# Pg2-Current_Sense.net
KiCad netlist of a schematic drawn in Altium Designer
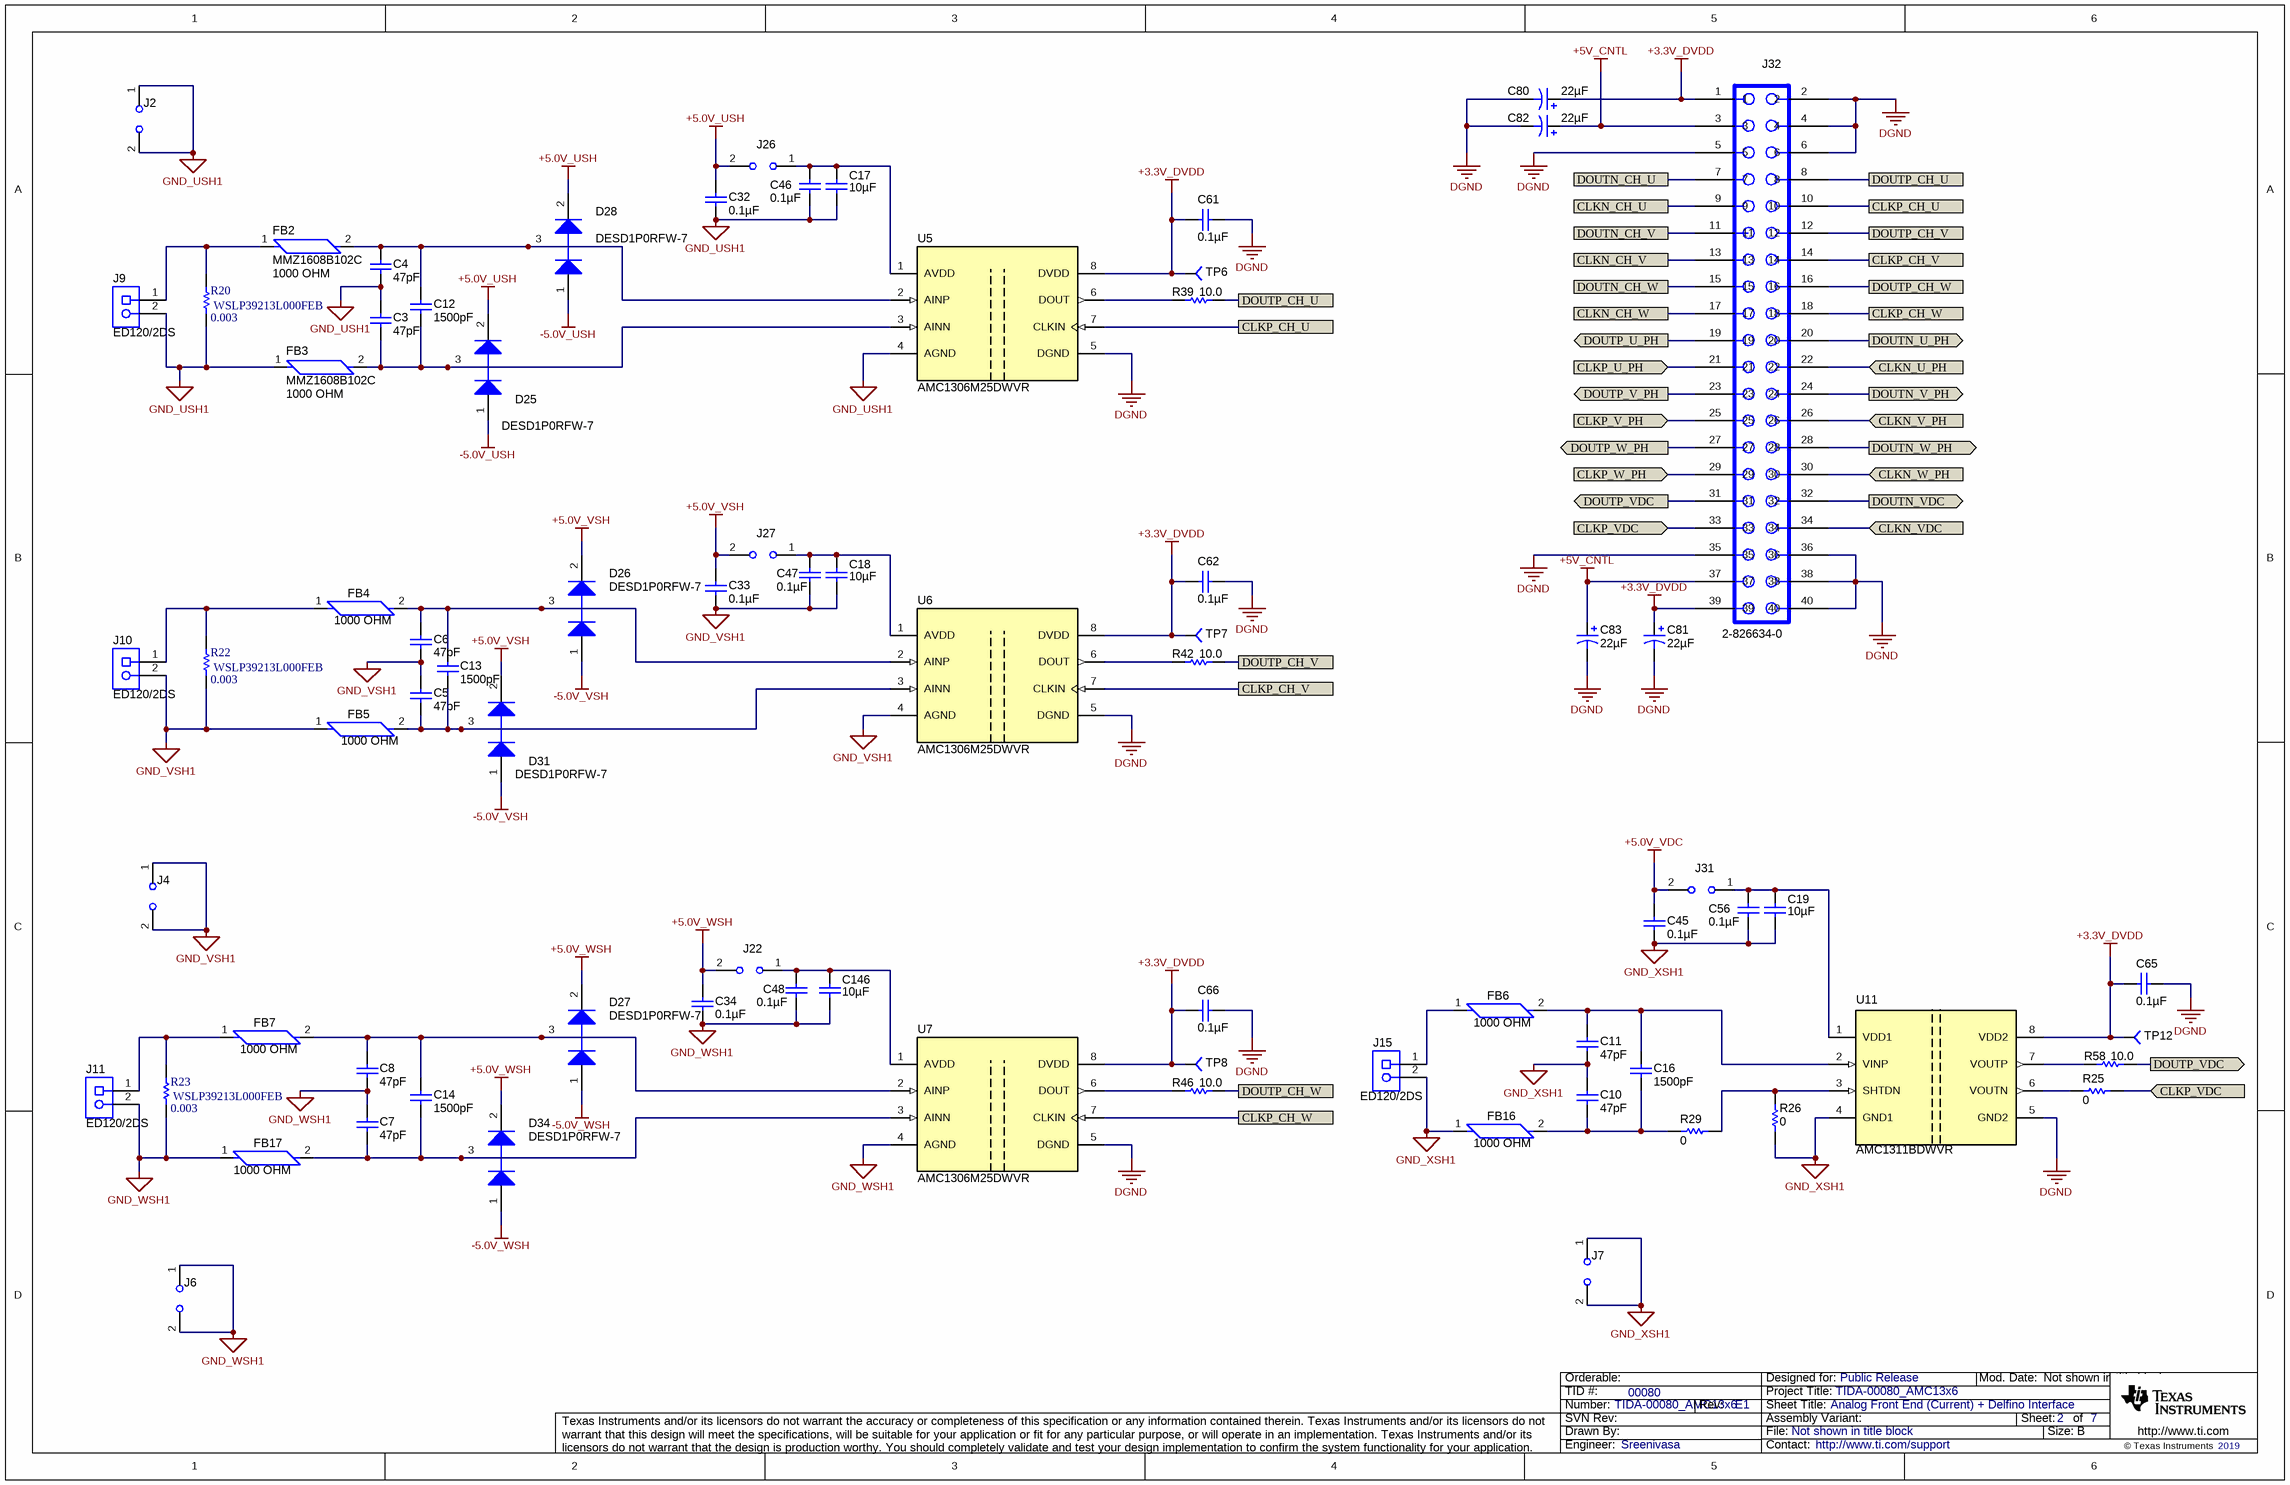
[diagram p0: Pg2-Current Sense.SchDoc]

(export (version "E")
  (design (tool "Eeschema 10.0.6"))
  (components
    (comp (ref "C3")
      (value "GRM21A5C2E470JW01D")
      (footprint "ISE_MCS_SDM_E1_20MAY:0805_HV")
      (description "CAP, CERM, 47pF, 500V, +/-5%, C0G/NP0, 0805")
      (fields
        (field (name "VALUEDISPLAYED") "47pF")
        (field (name "MANUFACTURER") "MuRata")
        (field (name "PUBLISHER") "Texas Instruments")
      )
      (libsource (lib "Capacitor_Ceramic") (part "GRM21A5C2E470JW01D"))
    )
    (comp (ref "C4")
      (value "GRM21A5C2E470JW01D")
      (footprint "ISE_MCS_SDM_E1_20MAY:0805_HV")
      (description "CAP, CERM, 47pF, 500V, +/-5%, C0G/NP0, 0805")
      (fields
        (field (name "VALUEDISPLAYED") "47pF")
        (field (name "MANUFACTURER") "MuRata")
        (field (name "PUBLISHER") "Texas Instruments")
      )
      (libsource (lib "Capacitor_Ceramic") (part "GRM21A5C2E470JW01D"))
    )
    (comp (ref "C5")
      (value "GRM21A5C2E470JW01D")
      (footprint "ISE_MCS_SDM_E1_20MAY:0805_HV")
      (description "CAP, CERM, 47pF, 500V, +/-5%, C0G/NP0, 0805")
      (fields
        (field (name "VALUEDISPLAYED") "47pF")
        (field (name "MANUFACTURER") "MuRata")
        (field (name "PUBLISHER") "Texas Instruments")
      )
      (libsource (lib "Capacitor_Ceramic") (part "GRM21A5C2E470JW01D"))
    )
    (comp (ref "C6")
      (value "GRM21A5C2E470JW01D")
      (footprint "ISE_MCS_SDM_E1_20MAY:0805_HV")
      (description "CAP, CERM, 47pF, 500V, +/-5%, C0G/NP0, 0805")
      (fields
        (field (name "VALUEDISPLAYED") "47pF")
        (field (name "MANUFACTURER") "MuRata")
        (field (name "PUBLISHER") "Texas Instruments")
      )
      (libsource (lib "Capacitor_Ceramic") (part "GRM21A5C2E470JW01D"))
    )
    (comp (ref "C7")
      (value "GRM21A5C2E470JW01D")
      (footprint "ISE_MCS_SDM_E1_20MAY:0805_HV")
      (description "CAP, CERM, 47pF, 500V, +/-5%, C0G/NP0, 0805")
      (fields
        (field (name "VALUEDISPLAYED") "47pF")
        (field (name "MANUFACTURER") "MuRata")
        (field (name "PUBLISHER") "Texas Instruments")
      )
      (libsource (lib "Capacitor_Ceramic") (part "GRM21A5C2E470JW01D"))
    )
    (comp (ref "C8")
      (value "GRM21A5C2E470JW01D")
      (footprint "ISE_MCS_SDM_E1_20MAY:0805_HV")
      (description "CAP, CERM, 47pF, 500V, +/-5%, C0G/NP0, 0805")
      (fields
        (field (name "VALUEDISPLAYED") "47pF")
        (field (name "MANUFACTURER") "MuRata")
        (field (name "PUBLISHER") "Texas Instruments")
      )
      (libsource (lib "Capacitor_Ceramic") (part "GRM21A5C2E470JW01D"))
    )
    (comp (ref "C10")
      (value "GRM21A5C2E470JW01D")
      (footprint "ISE_MCS_SDM_E1_20MAY:0805_HV")
      (description "CAP, CERM, 47pF, 500V, +/-5%, C0G/NP0, 0805")
      (fields
        (field (name "VALUEDISPLAYED") "47pF")
        (field (name "MANUFACTURER") "MuRata")
        (field (name "PUBLISHER") "Texas Instruments")
      )
      (libsource (lib "Capacitor_Ceramic") (part "GRM21A5C2E470JW01D"))
    )
    (comp (ref "C11")
      (value "GRM21A5C2E470JW01D")
      (footprint "ISE_MCS_SDM_E1_20MAY:0805_HV")
      (description "CAP, CERM, 47pF, 500V, +/-5%, C0G/NP0, 0805")
      (fields
        (field (name "VALUEDISPLAYED") "47pF")
        (field (name "MANUFACTURER") "MuRata")
        (field (name "PUBLISHER") "Texas Instruments")
      )
      (libsource (lib "Capacitor_Ceramic") (part "GRM21A5C2E470JW01D"))
    )
    (comp (ref "C12")
      (value "06031C152KAT2A")
      (footprint "ISE_MCS_SDM_E1_20MAY:0603")
      (description "CAP, CERM, 1500pF, 100V, +/-10%, X7R, 0603")
      (fields
        (field (name "VALUEDISPLAYED") "1500pF")
        (field (name "MANUFACTURER") "AVX")
        (field (name "PUBLISHER") "Texas Instruments")
      )
      (libsource (lib "Capacitor_Ceramic") (part "06031C152KAT2A"))
    )
    (comp (ref "C13")
      (value "06031C152KAT2A")
      (footprint "ISE_MCS_SDM_E1_20MAY:0603")
      (description "CAP, CERM, 1500pF, 100V, +/-10%, X7R, 0603")
      (fields
        (field (name "VALUEDISPLAYED") "1500pF")
        (field (name "MANUFACTURER") "AVX")
        (field (name "PUBLISHER") "Texas Instruments")
      )
      (libsource (lib "Capacitor_Ceramic") (part "06031C152KAT2A"))
    )
    (comp (ref "C14")
      (value "06031C152KAT2A")
      (footprint "ISE_MCS_SDM_E1_20MAY:0603")
      (description "CAP, CERM, 1500pF, 100V, +/-10%, X7R, 0603")
      (fields
        (field (name "VALUEDISPLAYED") "1500pF")
        (field (name "MANUFACTURER") "AVX")
        (field (name "PUBLISHER") "Texas Instruments")
      )
      (libsource (lib "Capacitor_Ceramic") (part "06031C152KAT2A"))
    )
    (comp (ref "C16")
      (value "06031C152KAT2A")
      (footprint "ISE_MCS_SDM_E1_20MAY:0603")
      (description "CAP, CERM, 1500pF, 100V, +/-10%, X7R, 0603")
      (fields
        (field (name "VALUEDISPLAYED") "1500pF")
        (field (name "MANUFACTURER") "AVX")
        (field (name "PUBLISHER") "Texas Instruments")
      )
      (libsource (lib "Capacitor_Ceramic") (part "06031C152KAT2A"))
    )
    (comp (ref "C17")
      (value "~")
      (footprint "1210")
      (description "CAP, CERM, 10uF, 35V, +/-20%, X7R, 1210")
      (fields
        (field (name "PARTNUMBER") "GMK325AB7106MM-T")
        (field (name "VALUEDISPLAYED") "10µF")
        (field (name "MANUFACTURER") "Taiyo Yuden")
        (field (name "PUBLISHER") "Texas Instruments")
      )
      (libsource (lib "Capacitor_Ceramic") (part "GMK325AB7106MM-T"))
    )
    (comp (ref "C18")
      (value "~")
      (footprint "1210")
      (description "CAP, CERM, 10uF, 35V, +/-20%, X7R, 1210")
      (fields
        (field (name "PARTNUMBER") "GMK325AB7106MM-T")
        (field (name "VALUEDISPLAYED") "10µF")
        (field (name "MANUFACTURER") "Taiyo Yuden")
        (field (name "PUBLISHER") "Texas Instruments")
      )
      (libsource (lib "Capacitor_Ceramic") (part "GMK325AB7106MM-T"))
    )
    (comp (ref "C19")
      (value "~")
      (footprint "1210")
      (description "CAP, CERM, 10uF, 35V, +/-20%, X7R, 1210")
      (fields
        (field (name "PARTNUMBER") "GMK325AB7106MM-T")
        (field (name "VALUEDISPLAYED") "10µF")
        (field (name "MANUFACTURER") "Taiyo Yuden")
        (field (name "PUBLISHER") "Texas Instruments")
      )
      (libsource (lib "Capacitor_Ceramic") (part "GMK325AB7106MM-T"))
    )
    (comp (ref "C32")
      (value "~")
      (footprint "ISE_MCS_SDM_E1_20MAY:0603")
      (description "CAP, CERM, 0.1uF, 50V, +/-10%, X7R, 0603")
      (fields
        (field (name "PARTNUMBER") "C0603C104K5RACTU")
        (field (name "VALUEDISPLAYED") "0.1µF")
        (field (name "MANUFACTURER") "Kemet")
        (field (name "PUBLISHER") "Texas Instruments")
      )
      (libsource (lib "Capacitor_Ceramic") (part "C0603C104K5RACTU"))
    )
    (comp (ref "C33")
      (value "~")
      (footprint "ISE_MCS_SDM_E1_20MAY:0603")
      (description "CAP, CERM, 0.1uF, 50V, +/-10%, X7R, 0603")
      (fields
        (field (name "PARTNUMBER") "C0603C104K5RACTU")
        (field (name "VALUEDISPLAYED") "0.1µF")
        (field (name "MANUFACTURER") "Kemet")
        (field (name "PUBLISHER") "Texas Instruments")
      )
      (libsource (lib "Capacitor_Ceramic") (part "C0603C104K5RACTU"))
    )
    (comp (ref "C34")
      (value "~")
      (footprint "ISE_MCS_SDM_E1_20MAY:0603")
      (description "CAP, CERM, 0.1uF, 50V, +/-10%, X7R, 0603")
      (fields
        (field (name "PARTNUMBER") "C0603C104K5RACTU")
        (field (name "VALUEDISPLAYED") "0.1µF")
        (field (name "MANUFACTURER") "Kemet")
        (field (name "PUBLISHER") "Texas Instruments")
      )
      (libsource (lib "Capacitor_Ceramic") (part "C0603C104K5RACTU"))
    )
    (comp (ref "C45")
      (value "~")
      (footprint "ISE_MCS_SDM_E1_20MAY:0603")
      (description "CAP, CERM, 0.1uF, 50V, +/-10%, X7R, 0603")
      (fields
        (field (name "PARTNUMBER") "C0603C104K5RACTU")
        (field (name "VALUEDISPLAYED") "0.1µF")
        (field (name "MANUFACTURER") "Kemet")
        (field (name "PUBLISHER") "Texas Instruments")
      )
      (libsource (lib "Capacitor_Ceramic") (part "C0603C104K5RACTU"))
    )
    (comp (ref "C46")
      (value "~")
      (footprint "ISE_MCS_SDM_E1_20MAY:0603")
      (description "CAP, CERM, 0.1uF, 50V, +/-10%, X7R, 0603")
      (fields
        (field (name "PARTNUMBER") "C0603C104K5RACTU")
        (field (name "VALUEDISPLAYED") "0.1µF")
        (field (name "MANUFACTURER") "Kemet")
        (field (name "PUBLISHER") "Texas Instruments")
      )
      (libsource (lib "Capacitor_Ceramic") (part "C0603C104K5RACTU"))
    )
    (comp (ref "C47")
      (value "~")
      (footprint "ISE_MCS_SDM_E1_20MAY:0603")
      (description "CAP, CERM, 0.1uF, 50V, +/-10%, X7R, 0603")
      (fields
        (field (name "PARTNUMBER") "C0603C104K5RACTU")
        (field (name "VALUEDISPLAYED") "0.1µF")
        (field (name "MANUFACTURER") "Kemet")
        (field (name "PUBLISHER") "Texas Instruments")
      )
      (libsource (lib "Capacitor_Ceramic") (part "C0603C104K5RACTU"))
    )
    (comp (ref "C48")
      (value "~")
      (footprint "ISE_MCS_SDM_E1_20MAY:0603")
      (description "CAP, CERM, 0.1uF, 50V, +/-10%, X7R, 0603")
      (fields
        (field (name "PARTNUMBER") "C0603C104K5RACTU")
        (field (name "VALUEDISPLAYED") "0.1µF")
        (field (name "MANUFACTURER") "Kemet")
        (field (name "PUBLISHER") "Texas Instruments")
      )
      (libsource (lib "Capacitor_Ceramic") (part "C0603C104K5RACTU"))
    )
    (comp (ref "C56")
      (value "~")
      (footprint "ISE_MCS_SDM_E1_20MAY:0603")
      (description "CAP, CERM, 0.1uF, 50V, +/-10%, X7R, 0603")
      (fields
        (field (name "PARTNUMBER") "C0603C104K5RACTU")
        (field (name "VALUEDISPLAYED") "0.1µF")
        (field (name "MANUFACTURER") "Kemet")
        (field (name "PUBLISHER") "Texas Instruments")
      )
      (libsource (lib "Capacitor_Ceramic") (part "C0603C104K5RACTU"))
    )
    (comp (ref "C61")
      (value "~")
      (footprint "ISE_MCS_SDM_E1_20MAY:0603")
      (description "CAP, CERM, 0.1uF, 25V, +/-5%, X7R, 0603")
      (fields
        (field (name "PARTNUMBER") "06033C104JAT2A")
        (field (name "VALUEDISPLAYED") "0.1µF")
        (field (name "MANUFACTURER") "AVX")
        (field (name "PUBLISHER") "Texas Instruments")
      )
      (libsource (lib "Capacitor_Ceramic") (part "06033C104JAT2A"))
    )
    (comp (ref "C62")
      (value "~")
      (footprint "ISE_MCS_SDM_E1_20MAY:0603")
      (description "CAP, CERM, 0.1uF, 25V, +/-5%, X7R, 0603")
      (fields
        (field (name "PARTNUMBER") "06033C104JAT2A")
        (field (name "VALUEDISPLAYED") "0.1µF")
        (field (name "MANUFACTURER") "AVX")
        (field (name "PUBLISHER") "Texas Instruments")
      )
      (libsource (lib "Capacitor_Ceramic") (part "06033C104JAT2A"))
    )
    (comp (ref "C65")
      (value "~")
      (footprint "ISE_MCS_SDM_E1_20MAY:0603")
      (description "CAP, CERM, 0.1uF, 25V, +/-5%, X7R, 0603")
      (fields
        (field (name "PARTNUMBER") "06033C104JAT2A")
        (field (name "VALUEDISPLAYED") "0.1µF")
        (field (name "MANUFACTURER") "AVX")
        (field (name "PUBLISHER") "Texas Instruments")
      )
      (libsource (lib "Capacitor_Ceramic") (part "06033C104JAT2A"))
    )
    (comp (ref "C66")
      (value "~")
      (footprint "ISE_MCS_SDM_E1_20MAY:0603")
      (description "CAP, CERM, 0.1uF, 25V, +/-5%, X7R, 0603")
      (fields
        (field (name "PARTNUMBER") "06033C104JAT2A")
        (field (name "VALUEDISPLAYED") "0.1µF")
        (field (name "MANUFACTURER") "AVX")
        (field (name "PUBLISHER") "Texas Instruments")
      )
      (libsource (lib "Capacitor_Ceramic") (part "06033C104JAT2A"))
    )
    (comp (ref "C80")
      (value "UUD1E220MCL1GS")
      (footprint "ISE_MCS_SDM_E1_20MAY:SM_RADIAL_5MM")
      (description "CAP, AL, 22uF, 25V, +/-20%, 0.76 ohm, SMD")
      (fields
        (field (name "VALUEDISPLAYED") "22µF")
        (field (name "MANUFACTURER") "Nichicon")
        (field (name "PUBLISHER") "Texas Instruments")
      )
      (libsource (lib "Capacitor_Aluminum") (part "UUD1E220MCL1GS"))
    )
    (comp (ref "C81")
      (value "UUD1E220MCL1GS")
      (footprint "ISE_MCS_SDM_E1_20MAY:SM_RADIAL_5MM")
      (description "CAP, AL, 22uF, 25V, +/-20%, 0.76 ohm, SMD")
      (fields
        (field (name "VALUEDISPLAYED") "22µF")
        (field (name "MANUFACTURER") "Nichicon")
        (field (name "PUBLISHER") "Texas Instruments")
      )
      (libsource (lib "Capacitor_Aluminum") (part "UUD1E220MCL1GS"))
    )
    (comp (ref "C82")
      (value "UUD1E220MCL1GS")
      (footprint "ISE_MCS_SDM_E1_20MAY:SM_RADIAL_5MM")
      (description "CAP, AL, 22uF, 25V, +/-20%, 0.76 ohm, SMD")
      (fields
        (field (name "VALUEDISPLAYED") "22µF")
        (field (name "MANUFACTURER") "Nichicon")
        (field (name "PUBLISHER") "Texas Instruments")
      )
      (libsource (lib "Capacitor_Aluminum") (part "UUD1E220MCL1GS"))
    )
    (comp (ref "C83")
      (value "UUD1E220MCL1GS")
      (footprint "ISE_MCS_SDM_E1_20MAY:SM_RADIAL_5MM")
      (description "CAP, AL, 22uF, 25V, +/-20%, 0.76 ohm, SMD")
      (fields
        (field (name "VALUEDISPLAYED") "22µF")
        (field (name "MANUFACTURER") "Nichicon")
        (field (name "PUBLISHER") "Texas Instruments")
      )
      (libsource (lib "Capacitor_Aluminum") (part "UUD1E220MCL1GS"))
    )
    (comp (ref "C146")
      (value "~")
      (footprint "1210")
      (description "CAP, CERM, 10uF, 35V, +/-20%, X7R, 1210")
      (fields
        (field (name "PARTNUMBER") "GMK325AB7106MM-T")
        (field (name "VALUEDISPLAYED") "10µF")
        (field (name "MANUFACTURER") "Taiyo Yuden")
        (field (name "PUBLISHER") "Texas Instruments")
      )
      (libsource (lib "Capacitor_Ceramic") (part "GMK325AB7106MM-T"))
    )
    (comp (ref "D25")
      (value "DESD1P0RFW-7")
      (footprint "ISE_MCS_SDM_E1_20MAY:SOT-323")
      (description "Diode, P-N, 70V, 0.2A, SOT-323")
      (fields (field (name "MANUFACTURER") "Diodes Inc") (field (name "PUBLISHER") "Texas Instruments"))
      (libsource (lib "Diode") (part "BAV99WT1G"))
    )
    (comp (ref "D26")
      (value "DESD1P0RFW-7")
      (footprint "ISE_MCS_SDM_E1_20MAY:SOT-323")
      (description "Diode, P-N, 70V, 0.2A, SOT-323")
      (fields (field (name "MANUFACTURER") "Diodes Inc") (field (name "PUBLISHER") "Texas Instruments"))
      (libsource (lib "Diode") (part "BAV99WT1G"))
    )
    (comp (ref "D27")
      (value "DESD1P0RFW-7")
      (footprint "ISE_MCS_SDM_E1_20MAY:SOT-323")
      (description "Diode, P-N, 70V, 0.2A, SOT-323")
      (fields (field (name "MANUFACTURER") "Diodes Inc") (field (name "PUBLISHER") "Texas Instruments"))
      (libsource (lib "Diode") (part "BAV99WT1G"))
    )
    (comp (ref "D28")
      (value "DESD1P0RFW-7")
      (footprint "ISE_MCS_SDM_E1_20MAY:SOT-323")
      (description "Diode, P-N, 70V, 0.2A, SOT-323")
      (fields (field (name "MANUFACTURER") "Diodes Inc") (field (name "PUBLISHER") "Texas Instruments"))
      (libsource (lib "Diode") (part "BAV99WT1G"))
    )
    (comp (ref "D31")
      (value "DESD1P0RFW-7")
      (footprint "ISE_MCS_SDM_E1_20MAY:SOT-323")
      (description "Diode, P-N, 70V, 0.2A, SOT-323")
      (fields (field (name "MANUFACTURER") "Diodes Inc") (field (name "PUBLISHER") "Texas Instruments"))
      (libsource (lib "Diode") (part "BAV99WT1G"))
    )
    (comp (ref "D34")
      (value "DESD1P0RFW-7")
      (footprint "ISE_MCS_SDM_E1_20MAY:SOT-323")
      (description "Diode, P-N, 70V, 0.2A, SOT-323")
      (fields (field (name "MANUFACTURER") "Diodes Inc") (field (name "PUBLISHER") "Texas Instruments"))
      (libsource (lib "Diode") (part "BAV99WT1G"))
    )
    (comp (ref "FB2")
      (value "MMZ1608B102C")
      (footprint "FB0603")
      (description "FERRITE CHIP 1000 OHM 300MA 0603")
      (fields
        (field (name "MANUFACTURER") "TDK Corporation")
        (field (name "ALTIUM_VALUE") "1000 OHM")
        (field (name "PUBLISHER") "TI")
      )
      (libsource (lib "Isolated current sensing") (part "MMZ1608B102C"))
    )
    (comp (ref "FB3")
      (value "MMZ1608B102C")
      (footprint "FB0603")
      (description "FERRITE CHIP 1000 OHM 300MA 0603")
      (fields
        (field (name "MANUFACTURER") "TDK Corporation")
        (field (name "ALTIUM_VALUE") "1000 OHM")
        (field (name "PUBLISHER") "TI")
      )
      (libsource (lib "Isolated current sensing") (part "MMZ1608B102C"))
    )
    (comp (ref "FB4")
      (value "1000 OHM")
      (footprint "FB0603")
      (description "FERRITE CHIP 1000 OHM 300MA 0603")
      (fields
        (field (name "PARTNUMBER") "MMZ1608B102C")
        (field (name "MANUFACTURER") "TDK Corporation")
        (field (name "PUBLISHER") "TI")
      )
      (libsource (lib "Isolated current sensing") (part "MMZ1608B102C"))
    )
    (comp (ref "FB5")
      (value "1000 OHM")
      (footprint "FB0603")
      (description "FERRITE CHIP 1000 OHM 300MA 0603")
      (fields
        (field (name "PARTNUMBER") "MMZ1608B102C")
        (field (name "MANUFACTURER") "TDK Corporation")
        (field (name "PUBLISHER") "TI")
      )
      (libsource (lib "Isolated current sensing") (part "MMZ1608B102C"))
    )
    (comp (ref "FB6")
      (value "1000 OHM")
      (footprint "FB0603")
      (description "FERRITE CHIP 1000 OHM 300MA 0603")
      (fields
        (field (name "PARTNUMBER") "MMZ1608B102C")
        (field (name "MANUFACTURER") "TDK Corporation")
        (field (name "PUBLISHER") "TI")
      )
      (libsource (lib "Isolated current sensing") (part "MMZ1608B102C"))
    )
    (comp (ref "FB7")
      (value "1000 OHM")
      (footprint "FB0603")
      (description "FERRITE CHIP 1000 OHM 300MA 0603")
      (fields
        (field (name "PARTNUMBER") "MMZ1608B102C")
        (field (name "MANUFACTURER") "TDK Corporation")
        (field (name "PUBLISHER") "TI")
      )
      (libsource (lib "Isolated current sensing") (part "MMZ1608B102C"))
    )
    (comp (ref "FB16")
      (value "1000 OHM")
      (footprint "FB0603")
      (description "FERRITE CHIP 1000 OHM 300MA 0603")
      (fields
        (field (name "PARTNUMBER") "MMZ1608B102C")
        (field (name "MANUFACTURER") "TDK Corporation")
        (field (name "PUBLISHER") "TI")
      )
      (libsource (lib "Isolated current sensing") (part "MMZ1608B102C"))
    )
    (comp (ref "FB17")
      (value "1000 OHM")
      (footprint "FB0603")
      (description "FERRITE CHIP 1000 OHM 300MA 0603")
      (fields
        (field (name "PARTNUMBER") "MMZ1608B102C")
        (field (name "MANUFACTURER") "TDK Corporation")
        (field (name "PUBLISHER") "TI")
      )
      (libsource (lib "Isolated current sensing") (part "MMZ1608B102C"))
    )
    (comp (ref "J2")
      (value "~")
      (footprint "ISE_MCS_SDM_E1_20MAY:HDR100_1X2")
      (description "Header, Male 2-pin, 100mil spacing,")
      (fields (field (name "MANUFACTURER") "FCI") (field (name "PARTNUMBER") "68001-402HLF"))
      (libsource (lib "PADSlegacy_Hardware") (part "JUMPER_2X100MIL"))
    )
    (comp (ref "J4")
      (value "~")
      (footprint "ISE_MCS_SDM_E1_20MAY:HDR100_1X2")
      (description "Header, Male 2-pin, 100mil spacing,")
      (fields (field (name "MANUFACTURER") "FCI") (field (name "PARTNUMBER") "68001-402HLF"))
      (libsource (lib "PADSlegacy_Hardware") (part "JUMPER_2X100MIL"))
    )
    (comp (ref "J6")
      (value "~")
      (footprint "ISE_MCS_SDM_E1_20MAY:HDR100_1X2")
      (description "Header, Male 2-pin, 100mil spacing,")
      (fields (field (name "MANUFACTURER") "FCI") (field (name "PARTNUMBER") "68001-402HLF"))
      (libsource (lib "PADSlegacy_Hardware") (part "JUMPER_2X100MIL"))
    )
    (comp (ref "J7")
      (value "~")
      (footprint "ISE_MCS_SDM_E1_20MAY:HDR100_1X2")
      (description "Header, Male 2-pin, 100mil spacing,")
      (fields (field (name "MANUFACTURER") "FCI") (field (name "PARTNUMBER") "68001-402HLF"))
      (libsource (lib "PADSlegacy_Hardware") (part "JUMPER_2X100MIL"))
    )
    (comp (ref "J9")
      (value "ED120/2DS")
      (footprint "ISE_MCS_SDM_E1_20MAY:CONN_ED120-2DS")
      (description "TERMINAL BLOCK 5.08MM VERT 2POS, TH")
      (fields
        (field (name "MANUFACTURER") "On-Shore Technology")
        (field (name "SYMBOLCREATOR") "a0412235")
        (field (name "PUBLISHER") "Texas Instruments")
      )
      (libsource (lib "Connectors") (part "ED120/2DS"))
    )
    (comp (ref "J10")
      (value "ED120/2DS")
      (footprint "ISE_MCS_SDM_E1_20MAY:CONN_ED120-2DS")
      (description "TERMINAL BLOCK 5.08MM VERT 2POS, TH")
      (fields
        (field (name "MANUFACTURER") "On-Shore Technology")
        (field (name "SYMBOLCREATOR") "a0412235")
        (field (name "PUBLISHER") "Texas Instruments")
      )
      (libsource (lib "Connectors") (part "ED120/2DS"))
    )
    (comp (ref "J11")
      (value "ED120/2DS")
      (footprint "ISE_MCS_SDM_E1_20MAY:CONN_ED120-2DS")
      (description "TERMINAL BLOCK 5.08MM VERT 2POS, TH")
      (fields
        (field (name "MANUFACTURER") "On-Shore Technology")
        (field (name "SYMBOLCREATOR") "a0412235")
        (field (name "PUBLISHER") "Texas Instruments")
      )
      (libsource (lib "Connectors") (part "ED120/2DS"))
    )
    (comp (ref "J15")
      (value "ED120/2DS")
      (footprint "ISE_MCS_SDM_E1_20MAY:CONN_ED120-2DS")
      (description "TERMINAL BLOCK 5.08MM VERT 2POS, TH")
      (fields
        (field (name "MANUFACTURER") "On-Shore Technology")
        (field (name "SYMBOLCREATOR") "a0412235")
        (field (name "PUBLISHER") "Texas Instruments")
      )
      (libsource (lib "Connectors") (part "ED120/2DS"))
    )
    (comp (ref "J22")
      (value "~")
      (footprint "ISE_MCS_SDM_E1_20MAY:HDR100_1X2")
      (description "Header, Male 2-pin, 100mil spacing,")
      (fields (field (name "MANUFACTURER") "FCI") (field (name "PARTNUMBER") "68001-402HLF"))
      (libsource (lib "PADSlegacy_Hardware") (part "JUMPER_2X100MIL"))
    )
    (comp (ref "J26")
      (value "~")
      (footprint "ISE_MCS_SDM_E1_20MAY:HDR100_1X2")
      (description "Header, Male 2-pin, 100mil spacing,")
      (fields (field (name "MANUFACTURER") "FCI") (field (name "PARTNUMBER") "68001-402HLF"))
      (libsource (lib "PADSlegacy_Hardware") (part "JUMPER_2X100MIL"))
    )
    (comp (ref "J27")
      (value "~")
      (footprint "ISE_MCS_SDM_E1_20MAY:HDR100_1X2")
      (description "Header, Male 2-pin, 100mil spacing,")
      (fields (field (name "MANUFACTURER") "FCI") (field (name "PARTNUMBER") "68001-402HLF"))
      (libsource (lib "PADSlegacy_Hardware") (part "JUMPER_2X100MIL"))
    )
    (comp (ref "J31")
      (value "~")
      (footprint "ISE_MCS_SDM_E1_20MAY:HDR100_1X2")
      (description "Header, Male 2-pin, 100mil spacing,")
      (fields (field (name "MANUFACTURER") "FCI") (field (name "PARTNUMBER") "68001-402HLF"))
      (libsource (lib "PADSlegacy_Hardware") (part "JUMPER_2X100MIL"))
    )
    (comp (ref "J32")
      (value "2-826634-0")
      (footprint "ISE_MCS_SDM_E1_20MAY:CONN_61304021021")
      (description "Connector, Right Angle 2x20 pin, 100mil spacing")
      (fields (field (name "MANUFACTURER") "TE Connectivity"))
      (libsource (lib "TI-INDIA-ALTIUM") (part "CONN_61304021021"))
    )
    (comp (ref "R20")
      (value "WSLP39213L000FEB")
      (footprint "RC3921")
      (description "RESISTOR, SMD, 0.003 OHM, 1%, 5W, 3921")
      (fields
        (field (name "MANUFACTURER") "VISHAY DALE")
        (field (name "ALTIUM_VALUE") "0.003")
        (field (name "SYMBOLCREATOR") "x0199378")
      )
      (libsource (lib "TS11406AC0_TIDA-00555") (part "WSLP39213L000FEB"))
    )
    (comp (ref "R22")
      (value "WSLP39213L000FEB")
      (footprint "RC3921")
      (description "RESISTOR, SMD, 0.003 OHM, 1%, 5W, 3921")
      (fields
        (field (name "MANUFACTURER") "VISHAY DALE")
        (field (name "ALTIUM_VALUE") "0.003")
        (field (name "SYMBOLCREATOR") "x0199378")
      )
      (libsource (lib "TS11406AC0_TIDA-00555") (part "WSLP39213L000FEB"))
    )
    (comp (ref "R23")
      (value "WSLP39213L000FEB")
      (footprint "RC3921")
      (description "RESISTOR, SMD, 0.003 OHM, 1%, 5W, 3921")
      (fields
        (field (name "MANUFACTURER") "VISHAY DALE")
        (field (name "ALTIUM_VALUE") "0.003")
        (field (name "SYMBOLCREATOR") "x0199378")
      )
      (libsource (lib "TS11406AC0_TIDA-00555") (part "WSLP39213L000FEB"))
    )
    (comp (ref "R25")
      (value "CRCW06030000Z0EA")
      (footprint "0603")
      (description "RES, 0, 5%, 0.1 W, 0603")
      (fields
        (field (name "VALUEDISPLAYED") "0")
        (field (name "MANUFACTURER") "Vishay-Dale")
        (field (name "PUBLISHER") "Texas Instruments")
      )
      (libsource (lib "Resistor_0603") (part "CRCW06030000Z0EA"))
    )
    (comp (ref "R26")
      (value "CRCW06030000Z0EA")
      (footprint "0603")
      (description "RES, 0, 5%, 0.1 W, 0603")
      (fields
        (field (name "VALUEDISPLAYED") "0")
        (field (name "MANUFACTURER") "Vishay-Dale")
        (field (name "PUBLISHER") "Texas Instruments")
      )
      (libsource (lib "Resistor_0603") (part "CRCW06030000Z0EA"))
    )
    (comp (ref "R29")
      (value "CRCW06030000Z0EA")
      (footprint "0603")
      (description "RES, 0, 5%, 0.1 W, 0603")
      (fields
        (field (name "VALUEDISPLAYED") "0")
        (field (name "MANUFACTURER") "Vishay-Dale")
        (field (name "PUBLISHER") "Texas Instruments")
      )
      (libsource (lib "Resistor_0603") (part "CRCW06030000Z0EA"))
    )
    (comp (ref "R39")
      (value "10.0")
      (footprint "ISE_MCS_SDM_E1_20MAY:0603")
      (description "RES, 10.0 ohm, 1%, 0.1W, 0603")
      (fields
        (field (name "PARTNUMBER") "CRCW060310R0FKEA")
        (field (name "MANUFACTURER") "Vishay-Dale")
        (field (name "PUBLISHER") "Texas Instruments")
      )
      (libsource (lib "Resistor_0603") (part "CRCW060310R0FKEA"))
    )
    (comp (ref "R42")
      (value "10.0")
      (footprint "ISE_MCS_SDM_E1_20MAY:0603")
      (description "RES, 10.0 ohm, 1%, 0.1W, 0603")
      (fields
        (field (name "PARTNUMBER") "CRCW060310R0FKEA")
        (field (name "MANUFACTURER") "Vishay-Dale")
        (field (name "PUBLISHER") "Texas Instruments")
      )
      (libsource (lib "Resistor_0603") (part "CRCW060310R0FKEA"))
    )
    (comp (ref "R46")
      (value "10.0")
      (footprint "ISE_MCS_SDM_E1_20MAY:0603")
      (description "RES, 10.0 ohm, 1%, 0.1W, 0603")
      (fields
        (field (name "PARTNUMBER") "CRCW060310R0FKEA")
        (field (name "MANUFACTURER") "Vishay-Dale")
        (field (name "PUBLISHER") "Texas Instruments")
      )
      (libsource (lib "Resistor_0603") (part "CRCW060310R0FKEA"))
    )
    (comp (ref "R58")
      (value "10.0")
      (footprint "ISE_MCS_SDM_E1_20MAY:0603")
      (description "RES, 10.0 ohm, 1%, 0.1W, 0603")
      (fields
        (field (name "PARTNUMBER") "CRCW060310R0FKEA")
        (field (name "MANUFACTURER") "Vishay-Dale")
        (field (name "PUBLISHER") "Texas Instruments")
      )
      (libsource (lib "Resistor_0603") (part "CRCW060310R0FKEA"))
    )
    (comp (ref "TP6")
      (value "~")
      (footprint "ISE_MCS_SDM_E1_20MAY:TP-040_RND")
      (description "Test Point, O.040 Hole")
      (fields (field (name "MANUFACTURER") "STD"))
      (libsource (lib "PADSlegacy_Hardware") (part "TP-040_RND"))
    )
    (comp (ref "TP7")
      (value "~")
      (footprint "ISE_MCS_SDM_E1_20MAY:TP-040_RND")
      (description "Test Point, O.040 Hole")
      (fields (field (name "MANUFACTURER") "STD"))
      (libsource (lib "PADSlegacy_Hardware") (part "TP-040_RND"))
    )
    (comp (ref "TP8")
      (value "~")
      (footprint "ISE_MCS_SDM_E1_20MAY:TP-040_RND")
      (description "Test Point, O.040 Hole")
      (fields (field (name "MANUFACTURER") "STD"))
      (libsource (lib "PADSlegacy_Hardware") (part "TP-040_RND"))
    )
    (comp (ref "TP12")
      (value "~")
      (footprint "ISE_MCS_SDM_E1_20MAY:TP-040_RND")
      (description "Test Point, O.040 Hole")
      (fields (field (name "MANUFACTURER") "STD"))
      (libsource (lib "PADSlegacy_Hardware") (part "TP-040_RND"))
    )
    (comp (ref "U5")
      (value "AMC1306M25DWVR")
      (footprint "DWV0008A")
      (description "Small Reinforced Isolated Modulator With +/-250mV Input and CMOS Interface, DWV0008A (SOIC-8)")
      (fields
        (field (name "ALTERNATE PARTNUMBER") "AMC1306M25DWV")
        (field (name "MANUFACTURER") "Texas Instruments")
        (field (name "SYMBOLCREATOR") "Altium")
        (field (name "PUBLISHER") "Texas Instruments")
      )
      (libsource (lib "TI_Pre_Release2") (part "AMC1306M25DWVR"))
    )
    (comp (ref "U6")
      (value "AMC1306M25DWVR")
      (footprint "DWV0008A")
      (description "Small Reinforced Isolated Modulator With +/-250mV Input and CMOS Interface, DWV0008A (SOIC-8)")
      (fields
        (field (name "ALTERNATE PARTNUMBER") "AMC1306M25DWV")
        (field (name "MANUFACTURER") "Texas Instruments")
        (field (name "SYMBOLCREATOR") "Altium")
        (field (name "PUBLISHER") "Texas Instruments")
      )
      (libsource (lib "TI_Pre_Release2") (part "AMC1306M25DWVR"))
    )
    (comp (ref "U7")
      (value "AMC1306M25DWVR")
      (footprint "DWV0008A")
      (description "Small Reinforced Isolated Modulator With +/-250mV Input and CMOS Interface, DWV0008A (SOIC-8)")
      (fields
        (field (name "ALTERNATE PARTNUMBER") "AMC1306M25DWV")
        (field (name "MANUFACTURER") "Texas Instruments")
        (field (name "SYMBOLCREATOR") "Altium")
        (field (name "PUBLISHER") "Texas Instruments")
      )
      (libsource (lib "TI_Pre_Release2") (part "AMC1306M25DWVR"))
    )
    (comp (ref "U11")
      (value "AMC1311BDWVR")
      (footprint "DWV0008A")
      (description "Precision, 2-V Input, Reinforced Isolated Amplifier, DWV0008A (SOIC-8)")
      (fields
        (field (name "ALTERNATE PARTNUMBER") "AMC1311DWV")
        (field (name "MANUFACTURER") "Texas Instruments")
        (field (name "SYMBOLCREATOR") "a0411947")
        (field (name "PUBLISHER") "Texas Instruments")
      )
      (libsource (lib "TI_Pre_RTM") (part "AMC1311DWVR"))
    )
  )
  (nets
    (net (code "1") (name "+3.3V_DVDD") (class "Default")
      (node (ref "C61") (pin "2") (pinfunction "2_2") (pintype "passive"))
      (node (ref "C62") (pin "2") (pinfunction "2_2") (pintype "passive"))
      (node (ref "C65") (pin "2") (pinfunction "2_2") (pintype "passive"))
      (node (ref "C66") (pin "2") (pinfunction "2_2") (pintype "passive"))
      (node (ref "C80") (pin "1") (pinfunction "+_1") (pintype "passive"))
      (node (ref "C81") (pin "1") (pinfunction "+_1") (pintype "passive"))
      (node (ref "J32") (pin "1") (pinfunction "1_1") (pintype "passive"))
      (node (ref "J32") (pin "39") (pinfunction "39_39") (pintype "passive"))
      (node (ref "TP12") (pin "1") (pinfunction "1_1") (pintype "passive"))
      (node (ref "TP6") (pin "1") (pinfunction "1_1") (pintype "passive"))
      (node (ref "TP7") (pin "1") (pinfunction "1_1") (pintype "passive"))
      (node (ref "TP8") (pin "1") (pinfunction "1_1") (pintype "passive"))
      (node (ref "U11") (pin "8") (pinfunction "VDD2_8") (pintype "power_in"))
      (node (ref "U5") (pin "8") (pinfunction "DVDD_8") (pintype "power_in"))
      (node (ref "U6") (pin "8") (pinfunction "DVDD_8") (pintype "power_in"))
      (node (ref "U7") (pin "8") (pinfunction "DVDD_8") (pintype "power_in"))
    )
    (net (code "2") (name "+5.0V_USH") (class "Default")
      (node (ref "C32") (pin "1") (pinfunction "1_1") (pintype "passive"))
      (node (ref "D25") (pin "2") (pinfunction "K_2") (pintype "passive"))
      (node (ref "D28") (pin "2") (pinfunction "K_2") (pintype "passive"))
      (node (ref "J26") (pin "2") (pintype "passive"))
    )
    (net (code "3") (name "+5.0V_VDC") (class "Default")
      (node (ref "C45") (pin "1") (pinfunction "1_1") (pintype "passive"))
      (node (ref "J31") (pin "2") (pintype "passive"))
    )
    (net (code "4") (name "+5.0V_VSH") (class "Default")
      (node (ref "C33") (pin "1") (pinfunction "1_1") (pintype "passive"))
      (node (ref "D26") (pin "2") (pinfunction "K_2") (pintype "passive"))
      (node (ref "D31") (pin "2") (pinfunction "K_2") (pintype "passive"))
      (node (ref "J27") (pin "2") (pintype "passive"))
    )
    (net (code "5") (name "+5.0V_WSH") (class "Default")
      (node (ref "C34") (pin "1") (pinfunction "1_1") (pintype "passive"))
      (node (ref "D27") (pin "2") (pinfunction "K_2") (pintype "passive"))
      (node (ref "D34") (pin "2") (pinfunction "K_2") (pintype "passive"))
      (node (ref "J22") (pin "2") (pintype "passive"))
    )
    (net (code "6") (name "+5V_CNTL") (class "Default")
      (node (ref "C82") (pin "1") (pinfunction "+_1") (pintype "passive"))
      (node (ref "C83") (pin "1") (pinfunction "+_1") (pintype "passive"))
      (node (ref "J32") (pin "3") (pinfunction "3_3") (pintype "passive"))
      (node (ref "J32") (pin "37") (pinfunction "37_37") (pintype "passive"))
    )
    (net (code "7") (name "-5.0V_USH") (class "Default")
      (node (ref "D25") (pin "1") (pinfunction "A_1") (pintype "passive"))
      (node (ref "D28") (pin "1") (pinfunction "A_1") (pintype "passive"))
    )
    (net (code "8") (name "-5.0V_VSH") (class "Default")
      (node (ref "D26") (pin "1") (pinfunction "A_1") (pintype "passive"))
      (node (ref "D31") (pin "1") (pinfunction "A_1") (pintype "passive"))
    )
    (net (code "9") (name "-5.0V_WSH") (class "Default")
      (node (ref "D27") (pin "1") (pinfunction "A_1") (pintype "passive"))
      (node (ref "D34") (pin "1") (pinfunction "A_1") (pintype "passive"))
    )
    (net (code "10") (name "/CLKN_CH_U") (class "Default")
      (node (ref "J32") (pin "9") (pinfunction "9_9") (pintype "passive"))
    )
    (net (code "11") (name "/CLKN_CH_V") (class "Default")
      (node (ref "J32") (pin "13") (pinfunction "13_13") (pintype "passive"))
    )
    (net (code "12") (name "/CLKN_CH_W") (class "Default")
      (node (ref "J32") (pin "17") (pinfunction "17_17") (pintype "passive"))
    )
    (net (code "13") (name "/CLKN_U_PH") (class "Default")
      (node (ref "J32") (pin "22") (pinfunction "22_22") (pintype "passive"))
    )
    (net (code "14") (name "/CLKN_VDC") (class "Default")
      (node (ref "J32") (pin "34") (pinfunction "34_34") (pintype "passive"))
    )
    (net (code "15") (name "/CLKN_V_PH") (class "Default")
      (node (ref "J32") (pin "26") (pinfunction "26_26") (pintype "passive"))
    )
    (net (code "16") (name "/CLKN_W_PH") (class "Default")
      (node (ref "J32") (pin "30") (pinfunction "30_30") (pintype "passive"))
    )
    (net (code "17") (name "/CLKP_CH_U") (class "Default")
      (node (ref "J32") (pin "10") (pinfunction "10_10") (pintype "passive"))
      (node (ref "U5") (pin "7") (pinfunction "CLKIN_7") (pintype "input"))
    )
    (net (code "18") (name "/CLKP_CH_V") (class "Default")
      (node (ref "J32") (pin "14") (pinfunction "14_14") (pintype "passive"))
      (node (ref "U6") (pin "7") (pinfunction "CLKIN_7") (pintype "input"))
    )
    (net (code "19") (name "/CLKP_CH_W") (class "Default")
      (node (ref "J32") (pin "18") (pinfunction "18_18") (pintype "passive"))
      (node (ref "U7") (pin "7") (pinfunction "CLKIN_7") (pintype "input"))
    )
    (net (code "20") (name "/CLKP_U_PH") (class "Default")
      (node (ref "J32") (pin "21") (pinfunction "21_21") (pintype "passive"))
    )
    (net (code "21") (name "/CLKP_VDC") (class "Default")
      (node (ref "J32") (pin "33") (pinfunction "33_33") (pintype "passive"))
      (node (ref "R25") (pin "1") (pinfunction "1_1") (pintype "passive"))
    )
    (net (code "22") (name "/CLKP_V_PH") (class "Default")
      (node (ref "J32") (pin "25") (pinfunction "25_25") (pintype "passive"))
    )
    (net (code "23") (name "/CLKP_W_PH") (class "Default")
      (node (ref "J32") (pin "29") (pinfunction "29_29") (pintype "passive"))
    )
    (net (code "24") (name "/DOUTN_CH_U") (class "Default")
      (node (ref "J32") (pin "7") (pinfunction "7_7") (pintype "passive"))
    )
    (net (code "25") (name "/DOUTN_CH_V") (class "Default")
      (node (ref "J32") (pin "11") (pinfunction "11_11") (pintype "passive"))
    )
    (net (code "26") (name "/DOUTN_CH_W") (class "Default")
      (node (ref "J32") (pin "15") (pinfunction "15_15") (pintype "passive"))
    )
    (net (code "27") (name "/DOUTN_U_PH") (class "Default")
      (node (ref "J32") (pin "20") (pinfunction "20_20") (pintype "passive"))
    )
    (net (code "28") (name "/DOUTN_VDC") (class "Default")
      (node (ref "J32") (pin "32") (pinfunction "32_32") (pintype "passive"))
    )
    (net (code "29") (name "/DOUTN_V_PH") (class "Default")
      (node (ref "J32") (pin "24") (pinfunction "24_24") (pintype "passive"))
    )
    (net (code "30") (name "/DOUTN_W_PH") (class "Default")
      (node (ref "J32") (pin "28") (pinfunction "28_28") (pintype "passive"))
    )
    (net (code "31") (name "/DOUTP_CH_U") (class "Default")
      (node (ref "J32") (pin "8") (pinfunction "8_8") (pintype "passive"))
      (node (ref "R39") (pin "2") (pinfunction "2_2") (pintype "passive"))
    )
    (net (code "32") (name "/DOUTP_CH_V") (class "Default")
      (node (ref "J32") (pin "12") (pinfunction "12_12") (pintype "passive"))
      (node (ref "R42") (pin "2") (pinfunction "2_2") (pintype "passive"))
    )
    (net (code "33") (name "/DOUTP_CH_W") (class "Default")
      (node (ref "J32") (pin "16") (pinfunction "16_16") (pintype "passive"))
      (node (ref "R46") (pin "2") (pinfunction "2_2") (pintype "passive"))
    )
    (net (code "34") (name "/DOUTP_U_PH") (class "Default")
      (node (ref "J32") (pin "19") (pinfunction "19_19") (pintype "passive"))
    )
    (net (code "35") (name "/DOUTP_VDC") (class "Default")
      (node (ref "J32") (pin "31") (pinfunction "31_31") (pintype "passive"))
      (node (ref "R58") (pin "2") (pinfunction "2_2") (pintype "passive"))
    )
    (net (code "36") (name "/DOUTP_V_PH") (class "Default")
      (node (ref "J32") (pin "23") (pinfunction "23_23") (pintype "passive"))
    )
    (net (code "37") (name "/DOUTP_W_PH") (class "Default")
      (node (ref "J32") (pin "27") (pinfunction "27_27") (pintype "passive"))
    )
    (net (code "38") (name "DGND") (class "Default")
      (node (ref "C61") (pin "1") (pinfunction "1_1") (pintype "passive"))
      (node (ref "C62") (pin "1") (pinfunction "1_1") (pintype "passive"))
      (node (ref "C65") (pin "1") (pinfunction "1_1") (pintype "passive"))
      (node (ref "C66") (pin "1") (pinfunction "1_1") (pintype "passive"))
      (node (ref "C80") (pin "2") (pinfunction "-_2") (pintype "passive"))
      (node (ref "C81") (pin "2") (pinfunction "-_2") (pintype "passive"))
      (node (ref "C82") (pin "2") (pinfunction "-_2") (pintype "passive"))
      (node (ref "C83") (pin "2") (pinfunction "-_2") (pintype "passive"))
      (node (ref "J32") (pin "2") (pinfunction "2_2") (pintype "passive"))
      (node (ref "J32") (pin "35") (pinfunction "35_35") (pintype "passive"))
      (node (ref "J32") (pin "36") (pinfunction "36_36") (pintype "passive"))
      (node (ref "J32") (pin "38") (pinfunction "38_38") (pintype "passive"))
      (node (ref "J32") (pin "4") (pinfunction "4_4") (pintype "passive"))
      (node (ref "J32") (pin "40") (pinfunction "40_40") (pintype "passive"))
      (node (ref "J32") (pin "5") (pinfunction "5_5") (pintype "passive"))
      (node (ref "J32") (pin "6") (pinfunction "6_6") (pintype "passive"))
      (node (ref "U11") (pin "5") (pinfunction "GND2_5") (pintype "power_in"))
      (node (ref "U5") (pin "5") (pinfunction "DGND_5") (pintype "power_in"))
      (node (ref "U6") (pin "5") (pinfunction "DGND_5") (pintype "power_in"))
      (node (ref "U7") (pin "5") (pinfunction "DGND_5") (pintype "power_in"))
    )
    (net (code "39") (name "GND_USH1") (class "Default")
      (node (ref "C17") (pin "1") (pinfunction "1_1") (pintype "passive"))
      (node (ref "C3") (pin "1") (pinfunction "1_1") (pintype "passive"))
      (node (ref "C32") (pin "2") (pinfunction "2_2") (pintype "passive"))
      (node (ref "C4") (pin "2") (pinfunction "2_2") (pintype "passive"))
      (node (ref "C46") (pin "2") (pinfunction "2_2") (pintype "passive"))
      (node (ref "FB3") (pin "1") (pinfunction "1_1") (pintype "passive"))
      (node (ref "J2") (pin "1") (pintype "passive"))
      (node (ref "J2") (pin "2") (pintype "passive"))
      (node (ref "J9") (pin "2") (pinfunction "2_2") (pintype "passive"))
      (node (ref "R20") (pin "1") (pinfunction "1_1") (pintype "passive"))
      (node (ref "U5") (pin "4") (pinfunction "AGND_4") (pintype "power_in"))
    )
    (net (code "40") (name "GND_VSH1") (class "Default")
      (node (ref "C18") (pin "1") (pinfunction "1_1") (pintype "passive"))
      (node (ref "C33") (pin "2") (pinfunction "2_2") (pintype "passive"))
      (node (ref "C47") (pin "2") (pinfunction "2_2") (pintype "passive"))
      (node (ref "C5") (pin "1") (pinfunction "1_1") (pintype "passive"))
      (node (ref "C6") (pin "2") (pinfunction "2_2") (pintype "passive"))
      (node (ref "FB5") (pin "1") (pinfunction "1_1") (pintype "passive"))
      (node (ref "J10") (pin "2") (pinfunction "2_2") (pintype "passive"))
      (node (ref "J4") (pin "1") (pintype "passive"))
      (node (ref "J4") (pin "2") (pintype "passive"))
      (node (ref "R22") (pin "1") (pinfunction "1_1") (pintype "passive"))
      (node (ref "U6") (pin "4") (pinfunction "AGND_4") (pintype "power_in"))
    )
    (net (code "41") (name "GND_WSH1") (class "Default")
      (node (ref "C146") (pin "1") (pinfunction "1_1") (pintype "passive"))
      (node (ref "C34") (pin "2") (pinfunction "2_2") (pintype "passive"))
      (node (ref "C48") (pin "2") (pinfunction "2_2") (pintype "passive"))
      (node (ref "C7") (pin "1") (pinfunction "1_1") (pintype "passive"))
      (node (ref "C8") (pin "2") (pinfunction "2_2") (pintype "passive"))
      (node (ref "FB17") (pin "1") (pinfunction "1_1") (pintype "passive"))
      (node (ref "J11") (pin "2") (pinfunction "2_2") (pintype "passive"))
      (node (ref "J6") (pin "1") (pintype "passive"))
      (node (ref "J6") (pin "2") (pintype "passive"))
      (node (ref "R23") (pin "1") (pinfunction "1_1") (pintype "passive"))
      (node (ref "U7") (pin "4") (pinfunction "AGND_4") (pintype "power_in"))
    )
    (net (code "42") (name "GND_XSH1") (class "Default")
      (node (ref "C10") (pin "1") (pinfunction "1_1") (pintype "passive"))
      (node (ref "C11") (pin "2") (pinfunction "2_2") (pintype "passive"))
      (node (ref "C19") (pin "1") (pinfunction "1_1") (pintype "passive"))
      (node (ref "C45") (pin "2") (pinfunction "2_2") (pintype "passive"))
      (node (ref "C56") (pin "2") (pinfunction "2_2") (pintype "passive"))
      (node (ref "FB16") (pin "1") (pinfunction "1_1") (pintype "passive"))
      (node (ref "J15") (pin "2") (pinfunction "2_2") (pintype "passive"))
      (node (ref "J7") (pin "1") (pintype "passive"))
      (node (ref "J7") (pin "2") (pintype "passive"))
      (node (ref "R26") (pin "1") (pinfunction "1_1") (pintype "passive"))
      (node (ref "U11") (pin "4") (pinfunction "GND1_4") (pintype "power_in"))
    )
    (net (code "43") (name "Net-(C10-Pad2)") (class "Default")
      (node (ref "C10") (pin "2") (pinfunction "2_2") (pintype "passive"))
      (node (ref "C16") (pin "2") (pinfunction "2_2") (pintype "passive"))
      (node (ref "FB16") (pin "2") (pinfunction "2_2") (pintype "passive"))
      (node (ref "R29") (pin "2") (pinfunction "2_2") (pintype "passive"))
    )
    (net (code "44") (name "Net-(D25-C)") (class "Default")
      (node (ref "C12") (pin "2") (pinfunction "2_2") (pintype "passive"))
      (node (ref "C3") (pin "2") (pinfunction "2_2") (pintype "passive"))
      (node (ref "D25") (pin "3") (pinfunction "C_3") (pintype "passive"))
      (node (ref "FB3") (pin "2") (pinfunction "2_2") (pintype "passive"))
      (node (ref "U5") (pin "3") (pinfunction "AINN_3") (pintype "input"))
    )
    (net (code "45") (name "Net-(D26-C)") (class "Default")
      (node (ref "C13") (pin "1") (pinfunction "1_1") (pintype "passive"))
      (node (ref "C6") (pin "1") (pinfunction "1_1") (pintype "passive"))
      (node (ref "D26") (pin "3") (pinfunction "C_3") (pintype "passive"))
      (node (ref "FB4") (pin "2") (pinfunction "2_2") (pintype "passive"))
      (node (ref "U6") (pin "2") (pinfunction "AINP_2") (pintype "input"))
    )
    (net (code "46") (name "Net-(D27-C)") (class "Default")
      (node (ref "C14") (pin "1") (pinfunction "1_1") (pintype "passive"))
      (node (ref "C8") (pin "1") (pinfunction "1_1") (pintype "passive"))
      (node (ref "D27") (pin "3") (pinfunction "C_3") (pintype "passive"))
      (node (ref "FB7") (pin "2") (pinfunction "2_2") (pintype "passive"))
      (node (ref "U7") (pin "2") (pinfunction "AINP_2") (pintype "input"))
    )
    (net (code "47") (name "Net-(D28-C)") (class "Default")
      (node (ref "C12") (pin "1") (pinfunction "1_1") (pintype "passive"))
      (node (ref "C4") (pin "1") (pinfunction "1_1") (pintype "passive"))
      (node (ref "D28") (pin "3") (pinfunction "C_3") (pintype "passive"))
      (node (ref "FB2") (pin "2") (pinfunction "2_2") (pintype "passive"))
      (node (ref "U5") (pin "2") (pinfunction "AINP_2") (pintype "input"))
    )
    (net (code "48") (name "Net-(D31-C)") (class "Default")
      (node (ref "C13") (pin "2") (pinfunction "2_2") (pintype "passive"))
      (node (ref "C5") (pin "2") (pinfunction "2_2") (pintype "passive"))
      (node (ref "D31") (pin "3") (pinfunction "C_3") (pintype "passive"))
      (node (ref "FB5") (pin "2") (pinfunction "2_2") (pintype "passive"))
      (node (ref "U6") (pin "3") (pinfunction "AINN_3") (pintype "input"))
    )
    (net (code "49") (name "Net-(D34-C)") (class "Default")
      (node (ref "C14") (pin "2") (pinfunction "2_2") (pintype "passive"))
      (node (ref "C7") (pin "2") (pinfunction "2_2") (pintype "passive"))
      (node (ref "D34") (pin "3") (pinfunction "C_3") (pintype "passive"))
      (node (ref "FB17") (pin "2") (pinfunction "2_2") (pintype "passive"))
      (node (ref "U7") (pin "3") (pinfunction "AINN_3") (pintype "input"))
    )
    (net (code "50") (name "Net-(FB2-Pad1)") (class "Default")
      (node (ref "FB2") (pin "1") (pinfunction "1_1") (pintype "passive"))
      (node (ref "J9") (pin "1") (pinfunction "1_1") (pintype "passive"))
      (node (ref "R20") (pin "2") (pinfunction "2_2") (pintype "passive"))
    )
    (net (code "51") (name "Net-(FB4-Pad1)") (class "Default")
      (node (ref "FB4") (pin "1") (pinfunction "1_1") (pintype "passive"))
      (node (ref "J10") (pin "1") (pinfunction "1_1") (pintype "passive"))
      (node (ref "R22") (pin "2") (pinfunction "2_2") (pintype "passive"))
    )
    (net (code "52") (name "Net-(FB6-Pad1)") (class "Default")
      (node (ref "FB6") (pin "1") (pinfunction "1_1") (pintype "passive"))
      (node (ref "J15") (pin "1") (pinfunction "1_1") (pintype "passive"))
    )
    (net (code "53") (name "Net-(FB7-Pad1)") (class "Default")
      (node (ref "FB7") (pin "1") (pinfunction "1_1") (pintype "passive"))
      (node (ref "J11") (pin "1") (pinfunction "1_1") (pintype "passive"))
      (node (ref "R23") (pin "2") (pinfunction "2_2") (pintype "passive"))
    )
    (net (code "54") (name "Net-(U5-AVDD)") (class "Default")
      (node (ref "C17") (pin "2") (pinfunction "2_2") (pintype "passive"))
      (node (ref "C46") (pin "1") (pinfunction "1_1") (pintype "passive"))
      (node (ref "J26") (pin "1") (pintype "passive"))
      (node (ref "U5") (pin "1") (pinfunction "AVDD_1") (pintype "power_in"))
    )
    (net (code "55") (name "Net-(U5-DOUT)") (class "Default")
      (node (ref "R39") (pin "1") (pinfunction "1_1") (pintype "passive"))
      (node (ref "U5") (pin "6") (pinfunction "DOUT_6") (pintype "output"))
    )
    (net (code "56") (name "Net-(U6-AVDD)") (class "Default")
      (node (ref "C18") (pin "2") (pinfunction "2_2") (pintype "passive"))
      (node (ref "C47") (pin "1") (pinfunction "1_1") (pintype "passive"))
      (node (ref "J27") (pin "1") (pintype "passive"))
      (node (ref "U6") (pin "1") (pinfunction "AVDD_1") (pintype "power_in"))
    )
    (net (code "57") (name "Net-(U6-DOUT)") (class "Default")
      (node (ref "R42") (pin "1") (pinfunction "1_1") (pintype "passive"))
      (node (ref "U6") (pin "6") (pinfunction "DOUT_6") (pintype "output"))
    )
    (net (code "58") (name "Net-(U7-AVDD)") (class "Default")
      (node (ref "C146") (pin "2") (pinfunction "2_2") (pintype "passive"))
      (node (ref "C48") (pin "1") (pinfunction "1_1") (pintype "passive"))
      (node (ref "J22") (pin "1") (pintype "passive"))
      (node (ref "U7") (pin "1") (pinfunction "AVDD_1") (pintype "power_in"))
    )
    (net (code "59") (name "Net-(U7-DOUT)") (class "Default")
      (node (ref "R46") (pin "1") (pinfunction "1_1") (pintype "passive"))
      (node (ref "U7") (pin "6") (pinfunction "DOUT_6") (pintype "output"))
    )
    (net (code "60") (name "Net-(U11-SHTDN)") (class "Default")
      (node (ref "R26") (pin "2") (pinfunction "2_2") (pintype "passive"))
      (node (ref "R29") (pin "1") (pinfunction "1_1") (pintype "passive"))
      (node (ref "U11") (pin "3") (pinfunction "SHTDN_3") (pintype "input"))
    )
    (net (code "61") (name "Net-(U11-VDD1)") (class "Default")
      (node (ref "C19") (pin "2") (pinfunction "2_2") (pintype "passive"))
      (node (ref "C56") (pin "1") (pinfunction "1_1") (pintype "passive"))
      (node (ref "J31") (pin "1") (pintype "passive"))
      (node (ref "U11") (pin "1") (pinfunction "VDD1_1") (pintype "power_in"))
    )
    (net (code "62") (name "Net-(U11-VINP)") (class "Default")
      (node (ref "C11") (pin "1") (pinfunction "1_1") (pintype "passive"))
      (node (ref "C16") (pin "1") (pinfunction "1_1") (pintype "passive"))
      (node (ref "FB6") (pin "2") (pinfunction "2_2") (pintype "passive"))
      (node (ref "U11") (pin "2") (pinfunction "VINP_2") (pintype "input"))
    )
    (net (code "63") (name "Net-(U11-VOUTN)") (class "Default")
      (node (ref "R25") (pin "2") (pinfunction "2_2") (pintype "passive"))
      (node (ref "U11") (pin "6") (pinfunction "VOUTN_6") (pintype "output"))
    )
    (net (code "64") (name "Net-(U11-VOUTP)") (class "Default")
      (node (ref "R58") (pin "1") (pinfunction "1_1") (pintype "passive"))
      (node (ref "U11") (pin "7") (pinfunction "VOUTP_7") (pintype "output"))
    )
  )
)
